# Switch_Output.net
KiCad netlist of a schematic drawn in Altium Designer
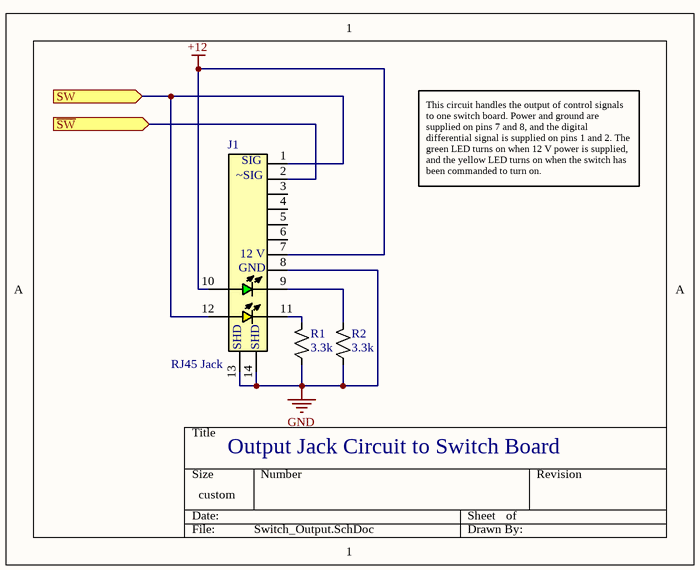
[diagram p0: Switch_Output.SchDoc]

(export (version "E")
  (design (tool "Eeschema 10.0.6"))
  (components
    (comp (ref "J1")
      (value "RJ45 Jack")
      (footprint "RJ45_JACK")
      (description "Jack RJ-45 8-pin")
      (libsource (lib "Load_Bank_New_IntLib") (part "J_RJ45_Jack"))
    )
    (comp (ref "R1")
      (value "3.3k")
      (footprint "0603_RES")
      (description "Resistor 3.3 kOhm 0603 1%")
      (libsource (lib "Load_Bank_New_IntLib") (part "R_3300Ohm_0603_1%"))
    )
    (comp (ref "R2")
      (value "3.3k")
      (footprint "0603_RES")
      (description "Resistor 3.3 kOhm 0603 1%")
      (libsource (lib "Load_Bank_New_IntLib") (part "R_3300Ohm_0603_1%"))
    )
  )
  (nets
    (net (code "1") (name "+12") (class "Default")
      (node (ref "J1") (pin "10") (pintype "passive"))
      (node (ref "J1") (pin "7") (pinfunction "12_V_7") (pintype "passive"))
    )
    (net (code "2") (name "/SW") (class "Default")
      (node (ref "J1") (pin "1") (pinfunction "Sig1_1") (pintype "passive"))
      (node (ref "J1") (pin "12") (pintype "passive"))
    )
    (net (code "3") (name "/~{SW}") (class "Default")
      (node (ref "J1") (pin "2") (pinfunction "Sig2_2") (pintype "passive"))
    )
    (net (code "4") (name "GND") (class "Default")
      (node (ref "J1") (pin "13") (pinfunction "SHD1_13") (pintype "passive"))
      (node (ref "J1") (pin "14") (pinfunction "SHD2_14") (pintype "passive"))
      (node (ref "J1") (pin "8") (pinfunction "GND_8") (pintype "passive"))
      (node (ref "R1") (pin "1") (pintype "passive"))
      (node (ref "R2") (pin "1") (pintype "passive"))
    )
    (net (code "5") (name "Net-(J1-Pad9)") (class "Default")
      (node (ref "J1") (pin "9") (pintype "passive"))
      (node (ref "R2") (pin "2") (pintype "passive"))
    )
    (net (code "6") (name "Net-(J1-Pad11)") (class "Default")
      (node (ref "J1") (pin "11") (pintype "passive"))
      (node (ref "R1") (pin "2") (pintype "passive"))
    )
    (net (code "7") (name "unconnected-(J1-NC-Pad3)") (class "Default")
      (node (ref "J1") (pin "3") (pinfunction "NC_3") (pintype "passive"))
    )
    (net (code "8") (name "unconnected-(J1-NC-Pad4)") (class "Default")
      (node (ref "J1") (pin "4") (pinfunction "NC_4") (pintype "passive"))
    )
    (net (code "9") (name "unconnected-(J1-NC-Pad5)") (class "Default")
      (node (ref "J1") (pin "5") (pinfunction "NC_5") (pintype "passive"))
    )
    (net (code "10") (name "unconnected-(J1-NC-Pad6)") (class "Default")
      (node (ref "J1") (pin "6") (pinfunction "NC_6") (pintype "passive"))
    )
  )
)
